# zik-pcb-base-gpu-bridge.net
KiCad netlist of a schematic drawn in EAGLE
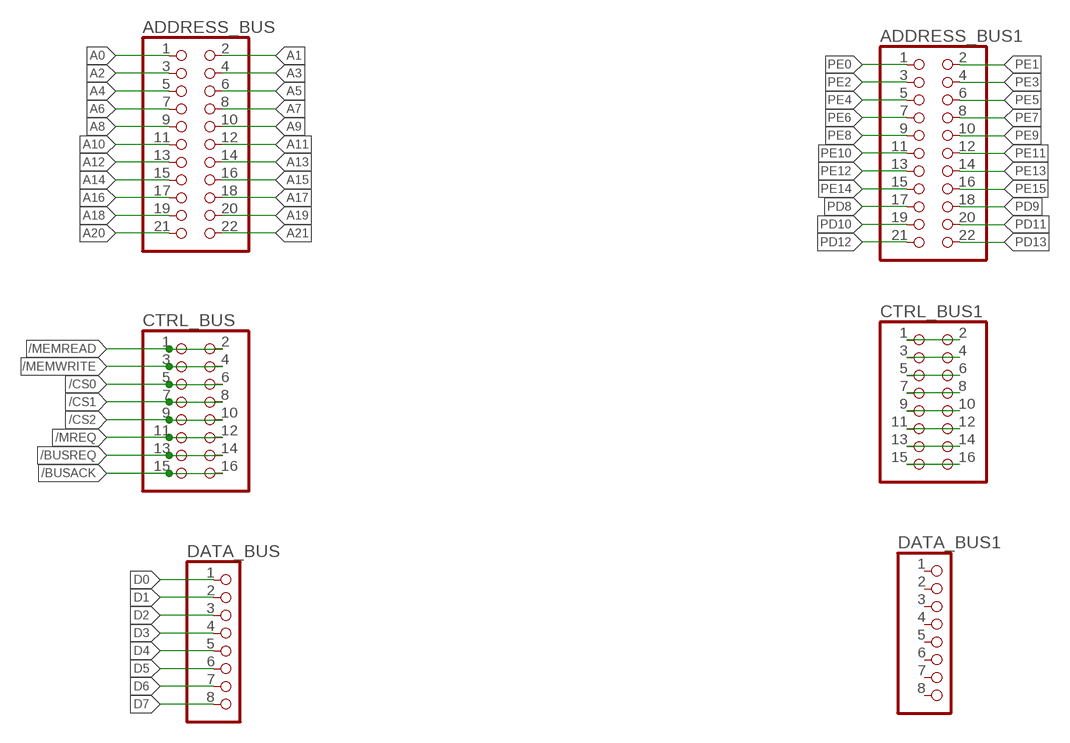
[diagram p0: schematic, sheet 1]

(export (version "E")
  (design (tool "Eeschema 10.0.6"))
  (components
    (comp (ref "ADDRESS_BUS")
      (value "PINHD-2X11")
      (footprint "eagle-import:2X11")
      (libsource (lib "eagle-import") (part "PINHD-2X11"))
    )
    (comp (ref "ADDRESS_BUS1")
      (value "PINHD-2X11")
      (footprint "eagle-import:2X11")
      (libsource (lib "eagle-import") (part "PINHD-2X11"))
    )
    (comp (ref "CTRL_BUS")
      (value "PINHD-2X8")
      (footprint "eagle-import:2X08")
      (libsource (lib "eagle-import") (part "PINHD-2X8"))
    )
    (comp (ref "CTRL_BUS1")
      (value "PINHD-2X8")
      (footprint "eagle-import:2X08")
      (libsource (lib "eagle-import") (part "PINHD-2X8"))
    )
    (comp (ref "DATA_BUS")
      (value "PINHD-1X8")
      (footprint "eagle-import:1X08")
      (libsource (lib "eagle-import") (part "PINHD-1X8"))
    )
    (comp (ref "DATA_BUS1")
      (value "PINHD-1X8")
      (footprint "eagle-import:1X08")
      (libsource (lib "eagle-import") (part "PINHD-1X8"))
    )
  )
  (nets
    (net (code "1") (name "A0") (class "Default")
      (node (ref "ADDRESS_BUS") (pin "1") (pinfunction "1_1") (pintype "passive"))
    )
    (net (code "2") (name "A1") (class "Default")
      (node (ref "ADDRESS_BUS") (pin "2") (pinfunction "2_2") (pintype "passive"))
    )
    (net (code "3") (name "A2") (class "Default")
      (node (ref "ADDRESS_BUS") (pin "3") (pinfunction "3_3") (pintype "passive"))
    )
    (net (code "4") (name "A3") (class "Default")
      (node (ref "ADDRESS_BUS") (pin "4") (pinfunction "4_4") (pintype "passive"))
    )
    (net (code "5") (name "A4") (class "Default")
      (node (ref "ADDRESS_BUS") (pin "5") (pinfunction "5_5") (pintype "passive"))
    )
    (net (code "6") (name "A5") (class "Default")
      (node (ref "ADDRESS_BUS") (pin "6") (pinfunction "6_6") (pintype "passive"))
    )
    (net (code "7") (name "A6") (class "Default")
      (node (ref "ADDRESS_BUS") (pin "7") (pinfunction "7_7") (pintype "passive"))
    )
    (net (code "8") (name "A7") (class "Default")
      (node (ref "ADDRESS_BUS") (pin "8") (pinfunction "8_8") (pintype "passive"))
    )
    (net (code "9") (name "A8") (class "Default")
      (node (ref "ADDRESS_BUS") (pin "9") (pinfunction "9_9") (pintype "passive"))
    )
    (net (code "10") (name "A9") (class "Default")
      (node (ref "ADDRESS_BUS") (pin "10") (pinfunction "10_10") (pintype "passive"))
    )
    (net (code "11") (name "A10") (class "Default")
      (node (ref "ADDRESS_BUS") (pin "11") (pinfunction "11_11") (pintype "passive"))
    )
    (net (code "12") (name "A11") (class "Default")
      (node (ref "ADDRESS_BUS") (pin "12") (pinfunction "12_12") (pintype "passive"))
    )
    (net (code "13") (name "A12") (class "Default")
      (node (ref "ADDRESS_BUS") (pin "13") (pinfunction "13_13") (pintype "passive"))
    )
    (net (code "14") (name "A13") (class "Default")
      (node (ref "ADDRESS_BUS") (pin "14") (pinfunction "14_14") (pintype "passive"))
    )
    (net (code "15") (name "A14") (class "Default")
      (node (ref "ADDRESS_BUS") (pin "15") (pinfunction "15_15") (pintype "passive"))
    )
    (net (code "16") (name "A15") (class "Default")
      (node (ref "ADDRESS_BUS") (pin "16") (pinfunction "16_16") (pintype "passive"))
    )
    (net (code "17") (name "A16") (class "Default")
      (node (ref "ADDRESS_BUS") (pin "17") (pinfunction "17_17") (pintype "passive"))
    )
    (net (code "18") (name "A17") (class "Default")
      (node (ref "ADDRESS_BUS") (pin "18") (pinfunction "18_18") (pintype "passive"))
    )
    (net (code "19") (name "A18") (class "Default")
      (node (ref "ADDRESS_BUS") (pin "19") (pinfunction "19_19") (pintype "passive"))
    )
    (net (code "20") (name "A19") (class "Default")
      (node (ref "ADDRESS_BUS") (pin "20") (pinfunction "20_20") (pintype "passive"))
    )
    (net (code "21") (name "A20") (class "Default")
      (node (ref "ADDRESS_BUS") (pin "21") (pinfunction "21_21") (pintype "passive"))
    )
    (net (code "22") (name "A21") (class "Default")
      (node (ref "ADDRESS_BUS") (pin "22") (pinfunction "22_22") (pintype "passive"))
    )
    (net (code "23") (name "D0") (class "Default")
      (node (ref "DATA_BUS") (pin "1") (pinfunction "1_1") (pintype "passive"))
    )
    (net (code "24") (name "D1") (class "Default")
      (node (ref "DATA_BUS") (pin "2") (pinfunction "2_2") (pintype "passive"))
    )
    (net (code "25") (name "D2") (class "Default")
      (node (ref "DATA_BUS") (pin "3") (pinfunction "3_3") (pintype "passive"))
    )
    (net (code "26") (name "D3") (class "Default")
      (node (ref "DATA_BUS") (pin "4") (pinfunction "4_4") (pintype "passive"))
    )
    (net (code "27") (name "D4") (class "Default")
      (node (ref "DATA_BUS") (pin "5") (pinfunction "5_5") (pintype "passive"))
    )
    (net (code "28") (name "D5") (class "Default")
      (node (ref "DATA_BUS") (pin "6") (pinfunction "6_6") (pintype "passive"))
    )
    (net (code "29") (name "D6") (class "Default")
      (node (ref "DATA_BUS") (pin "7") (pinfunction "7_7") (pintype "passive"))
    )
    (net (code "30") (name "D7") (class "Default")
      (node (ref "DATA_BUS") (pin "8") (pinfunction "8_8") (pintype "passive"))
    )
    (net (code "31") (name "Net-(CTRL_BUS1-Pad1)") (class "Default")
      (node (ref "CTRL_BUS1") (pin "1") (pinfunction "1_1") (pintype "passive"))
      (node (ref "CTRL_BUS1") (pin "2") (pinfunction "2_2") (pintype "passive"))
    )
    (net (code "32") (name "Net-(CTRL_BUS1-Pad3)") (class "Default")
      (node (ref "CTRL_BUS1") (pin "3") (pinfunction "3_3") (pintype "passive"))
      (node (ref "CTRL_BUS1") (pin "4") (pinfunction "4_4") (pintype "passive"))
    )
    (net (code "33") (name "Net-(CTRL_BUS1-Pad5)") (class "Default")
      (node (ref "CTRL_BUS1") (pin "5") (pinfunction "5_5") (pintype "passive"))
      (node (ref "CTRL_BUS1") (pin "6") (pinfunction "6_6") (pintype "passive"))
    )
    (net (code "34") (name "Net-(CTRL_BUS1-Pad7)") (class "Default")
      (node (ref "CTRL_BUS1") (pin "7") (pinfunction "7_7") (pintype "passive"))
      (node (ref "CTRL_BUS1") (pin "8") (pinfunction "8_8") (pintype "passive"))
    )
    (net (code "35") (name "Net-(CTRL_BUS1-Pad10)") (class "Default")
      (node (ref "CTRL_BUS1") (pin "10") (pinfunction "10_10") (pintype "passive"))
      (node (ref "CTRL_BUS1") (pin "9") (pinfunction "9_9") (pintype "passive"))
    )
    (net (code "36") (name "Net-(CTRL_BUS1-Pad11)") (class "Default")
      (node (ref "CTRL_BUS1") (pin "11") (pinfunction "11_11") (pintype "passive"))
      (node (ref "CTRL_BUS1") (pin "12") (pinfunction "12_12") (pintype "passive"))
    )
    (net (code "37") (name "Net-(CTRL_BUS1-Pad13)") (class "Default")
      (node (ref "CTRL_BUS1") (pin "13") (pinfunction "13_13") (pintype "passive"))
      (node (ref "CTRL_BUS1") (pin "14") (pinfunction "14_14") (pintype "passive"))
    )
    (net (code "38") (name "Net-(CTRL_BUS1-Pad15)") (class "Default")
      (node (ref "CTRL_BUS1") (pin "15") (pinfunction "15_15") (pintype "passive"))
      (node (ref "CTRL_BUS1") (pin "16") (pinfunction "16_16") (pintype "passive"))
    )
    (net (code "39") (name "PD8") (class "Default")
      (node (ref "ADDRESS_BUS1") (pin "17") (pinfunction "17_17") (pintype "passive"))
    )
    (net (code "40") (name "PD9") (class "Default")
      (node (ref "ADDRESS_BUS1") (pin "18") (pinfunction "18_18") (pintype "passive"))
    )
    (net (code "41") (name "PD10") (class "Default")
      (node (ref "ADDRESS_BUS1") (pin "19") (pinfunction "19_19") (pintype "passive"))
    )
    (net (code "42") (name "PD11") (class "Default")
      (node (ref "ADDRESS_BUS1") (pin "20") (pinfunction "20_20") (pintype "passive"))
    )
    (net (code "43") (name "PD12") (class "Default")
      (node (ref "ADDRESS_BUS1") (pin "21") (pinfunction "21_21") (pintype "passive"))
    )
    (net (code "44") (name "PD13") (class "Default")
      (node (ref "ADDRESS_BUS1") (pin "22") (pinfunction "22_22") (pintype "passive"))
    )
    (net (code "45") (name "PE0") (class "Default")
      (node (ref "ADDRESS_BUS1") (pin "1") (pinfunction "1_1") (pintype "passive"))
    )
    (net (code "46") (name "PE1") (class "Default")
      (node (ref "ADDRESS_BUS1") (pin "2") (pinfunction "2_2") (pintype "passive"))
    )
    (net (code "47") (name "PE2") (class "Default")
      (node (ref "ADDRESS_BUS1") (pin "3") (pinfunction "3_3") (pintype "passive"))
    )
    (net (code "48") (name "PE3") (class "Default")
      (node (ref "ADDRESS_BUS1") (pin "4") (pinfunction "4_4") (pintype "passive"))
    )
    (net (code "49") (name "PE4") (class "Default")
      (node (ref "ADDRESS_BUS1") (pin "5") (pinfunction "5_5") (pintype "passive"))
    )
    (net (code "50") (name "PE5") (class "Default")
      (node (ref "ADDRESS_BUS1") (pin "6") (pinfunction "6_6") (pintype "passive"))
    )
    (net (code "51") (name "PE6") (class "Default")
      (node (ref "ADDRESS_BUS1") (pin "7") (pinfunction "7_7") (pintype "passive"))
    )
    (net (code "52") (name "PE7") (class "Default")
      (node (ref "ADDRESS_BUS1") (pin "8") (pinfunction "8_8") (pintype "passive"))
    )
    (net (code "53") (name "PE8") (class "Default")
      (node (ref "ADDRESS_BUS1") (pin "9") (pinfunction "9_9") (pintype "passive"))
    )
    (net (code "54") (name "PE9") (class "Default")
      (node (ref "ADDRESS_BUS1") (pin "10") (pinfunction "10_10") (pintype "passive"))
    )
    (net (code "55") (name "PE10") (class "Default")
      (node (ref "ADDRESS_BUS1") (pin "11") (pinfunction "11_11") (pintype "passive"))
    )
    (net (code "56") (name "PE11") (class "Default")
      (node (ref "ADDRESS_BUS1") (pin "12") (pinfunction "12_12") (pintype "passive"))
    )
    (net (code "57") (name "PE12") (class "Default")
      (node (ref "ADDRESS_BUS1") (pin "13") (pinfunction "13_13") (pintype "passive"))
    )
    (net (code "58") (name "PE13") (class "Default")
      (node (ref "ADDRESS_BUS1") (pin "14") (pinfunction "14_14") (pintype "passive"))
    )
    (net (code "59") (name "PE14") (class "Default")
      (node (ref "ADDRESS_BUS1") (pin "15") (pinfunction "15_15") (pintype "passive"))
    )
    (net (code "60") (name "PE15") (class "Default")
      (node (ref "ADDRESS_BUS1") (pin "16") (pinfunction "16_16") (pintype "passive"))
    )
    (net (code "61") (name "unconnected-(DATA_BUS1-Pad1)") (class "Default")
      (node (ref "DATA_BUS1") (pin "1") (pinfunction "1_1") (pintype "passive"))
    )
    (net (code "62") (name "unconnected-(DATA_BUS1-Pad2)") (class "Default")
      (node (ref "DATA_BUS1") (pin "2") (pinfunction "2_2") (pintype "passive"))
    )
    (net (code "63") (name "unconnected-(DATA_BUS1-Pad3)") (class "Default")
      (node (ref "DATA_BUS1") (pin "3") (pinfunction "3_3") (pintype "passive"))
    )
    (net (code "64") (name "unconnected-(DATA_BUS1-Pad4)") (class "Default")
      (node (ref "DATA_BUS1") (pin "4") (pinfunction "4_4") (pintype "passive"))
    )
    (net (code "65") (name "unconnected-(DATA_BUS1-Pad5)") (class "Default")
      (node (ref "DATA_BUS1") (pin "5") (pinfunction "5_5") (pintype "passive"))
    )
    (net (code "66") (name "unconnected-(DATA_BUS1-Pad6)") (class "Default")
      (node (ref "DATA_BUS1") (pin "6") (pinfunction "6_6") (pintype "passive"))
    )
    (net (code "67") (name "unconnected-(DATA_BUS1-Pad7)") (class "Default")
      (node (ref "DATA_BUS1") (pin "7") (pinfunction "7_7") (pintype "passive"))
    )
    (net (code "68") (name "unconnected-(DATA_BUS1-Pad8)") (class "Default")
      (node (ref "DATA_BUS1") (pin "8") (pinfunction "8_8") (pintype "passive"))
    )
    (net (code "69") (name "{slash}BUSACK") (class "Default")
      (node (ref "CTRL_BUS") (pin "15") (pinfunction "15_15") (pintype "passive"))
      (node (ref "CTRL_BUS") (pin "16") (pinfunction "16_16") (pintype "passive"))
    )
    (net (code "70") (name "{slash}BUSREQ") (class "Default")
      (node (ref "CTRL_BUS") (pin "13") (pinfunction "13_13") (pintype "passive"))
      (node (ref "CTRL_BUS") (pin "14") (pinfunction "14_14") (pintype "passive"))
    )
    (net (code "71") (name "{slash}CS0") (class "Default")
      (node (ref "CTRL_BUS") (pin "5") (pinfunction "5_5") (pintype "passive"))
      (node (ref "CTRL_BUS") (pin "6") (pinfunction "6_6") (pintype "passive"))
    )
    (net (code "72") (name "{slash}CS1") (class "Default")
      (node (ref "CTRL_BUS") (pin "7") (pinfunction "7_7") (pintype "passive"))
      (node (ref "CTRL_BUS") (pin "8") (pinfunction "8_8") (pintype "passive"))
    )
    (net (code "73") (name "{slash}CS2") (class "Default")
      (node (ref "CTRL_BUS") (pin "10") (pinfunction "10_10") (pintype "passive"))
      (node (ref "CTRL_BUS") (pin "9") (pinfunction "9_9") (pintype "passive"))
    )
    (net (code "74") (name "{slash}MEMREAD") (class "Default")
      (node (ref "CTRL_BUS") (pin "1") (pinfunction "1_1") (pintype "passive"))
      (node (ref "CTRL_BUS") (pin "2") (pinfunction "2_2") (pintype "passive"))
    )
    (net (code "75") (name "{slash}MEMWRITE") (class "Default")
      (node (ref "CTRL_BUS") (pin "3") (pinfunction "3_3") (pintype "passive"))
      (node (ref "CTRL_BUS") (pin "4") (pinfunction "4_4") (pintype "passive"))
    )
    (net (code "76") (name "{slash}MREQ") (class "Default")
      (node (ref "CTRL_BUS") (pin "11") (pinfunction "11_11") (pintype "passive"))
      (node (ref "CTRL_BUS") (pin "12") (pinfunction "12_12") (pintype "passive"))
    )
  )
)
